# Module_Connector_Male.net
KiCad netlist of a schematic drawn in Altium Designer
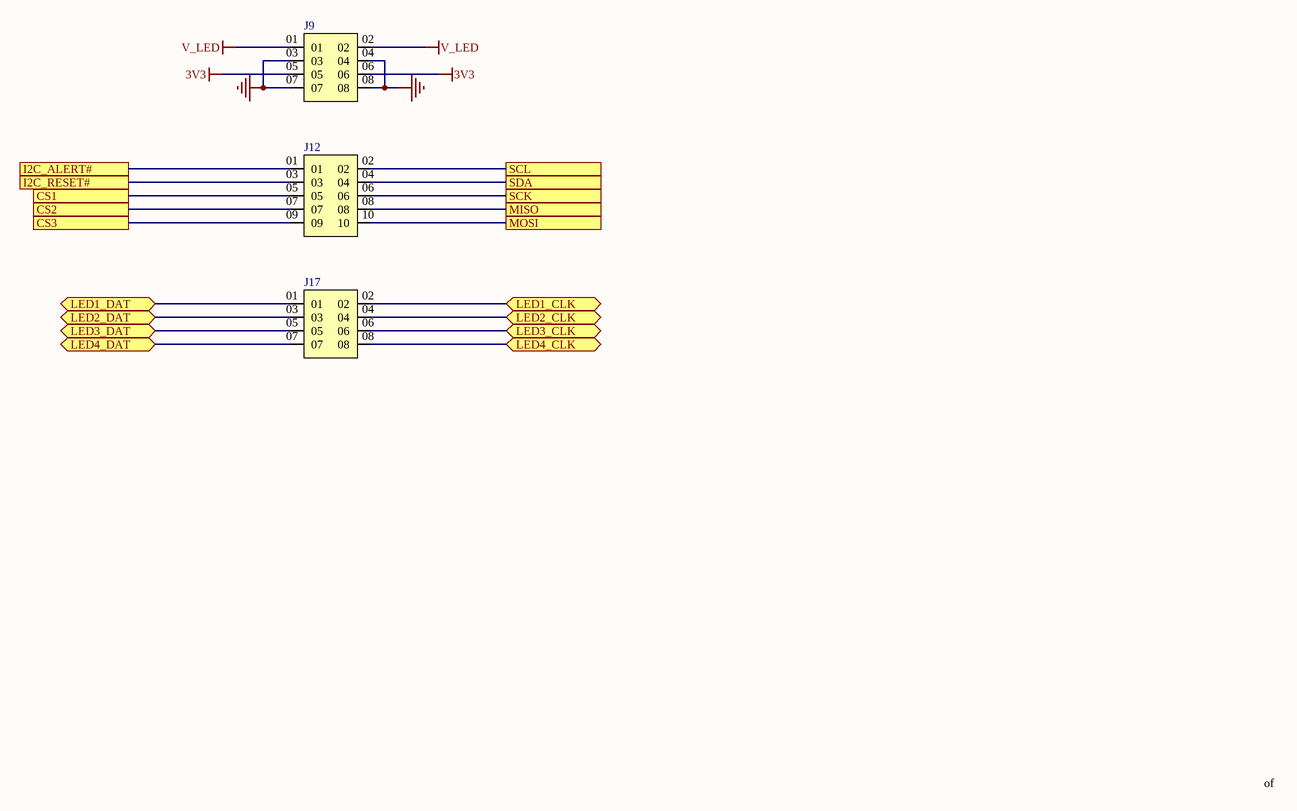
[diagram p0: Module Connector Male.SchDoc]

(export (version "E")
  (design (tool "Eeschema 10.0.6"))
  (components
    (comp (ref "J9")
      (value "Header 4x2 0.1\" RA")
      (footprint "Header 4x2 0.1\" RA")
      (description "Board Connector, 8 Contact(s), 2 Row(s), Female, Right Angle, 0.1 inch Pitch")
      (libsource (lib "Equus Computer Systems") (part "Header 4x2"))
    )
    (comp (ref "J12")
      (value "Header 5x2 0.1\" RA")
      (footprint "Header 5x2 0.1\" RA")
      (description "Board Connector, 10 Contact(s), 2 Row(s), Female, Right Angle, 0.1 inch Pitch")
      (libsource (lib "Equus Computer Systems") (part "Header 5x2 0.1{dblquote}"))
    )
    (comp (ref "J17")
      (value "Header 4x2 0.1\" RA")
      (footprint "Header 4x2 0.1\" RA")
      (description "Board Connector, 8 Contact(s), 2 Row(s), Female, Right Angle, 0.1 inch Pitch")
      (libsource (lib "Equus Computer Systems") (part "Header 4x2"))
    )
  )
  (nets
    (net (code "1") (name "/CS1") (class "Default")
      (node (ref "J12") (pin "05") (pinfunction "05_05") (pintype "passive"))
    )
    (net (code "2") (name "/CS2") (class "Default")
      (node (ref "J12") (pin "07") (pinfunction "07_07") (pintype "passive"))
    )
    (net (code "3") (name "/CS3") (class "Default")
      (node (ref "J12") (pin "09") (pinfunction "09_09") (pintype "passive"))
    )
    (net (code "4") (name "/I2C_ALERT#") (class "Default")
      (node (ref "J12") (pin "01") (pinfunction "01_01") (pintype "passive"))
    )
    (net (code "5") (name "/I2C_RESET#") (class "Default")
      (node (ref "J12") (pin "03") (pinfunction "03_03") (pintype "passive"))
    )
    (net (code "6") (name "/LED1_CLK") (class "Default")
      (node (ref "J17") (pin "02") (pinfunction "02_02") (pintype "passive"))
    )
    (net (code "7") (name "/LED1_DAT") (class "Default")
      (node (ref "J17") (pin "01") (pinfunction "01_01") (pintype "passive"))
    )
    (net (code "8") (name "/LED2_CLK") (class "Default")
      (node (ref "J17") (pin "04") (pinfunction "04_04") (pintype "passive"))
    )
    (net (code "9") (name "/LED2_DAT") (class "Default")
      (node (ref "J17") (pin "03") (pinfunction "03_03") (pintype "passive"))
    )
    (net (code "10") (name "/LED3_CLK") (class "Default")
      (node (ref "J17") (pin "06") (pinfunction "06_06") (pintype "passive"))
    )
    (net (code "11") (name "/LED3_DAT") (class "Default")
      (node (ref "J17") (pin "05") (pinfunction "05_05") (pintype "passive"))
    )
    (net (code "12") (name "/LED4_CLK") (class "Default")
      (node (ref "J17") (pin "08") (pinfunction "08_08") (pintype "passive"))
    )
    (net (code "13") (name "/LED4_DAT") (class "Default")
      (node (ref "J17") (pin "07") (pinfunction "07_07") (pintype "passive"))
    )
    (net (code "14") (name "/MISO") (class "Default")
      (node (ref "J12") (pin "08") (pinfunction "08_08") (pintype "passive"))
    )
    (net (code "15") (name "/MOSI") (class "Default")
      (node (ref "J12") (pin "10") (pinfunction "10_10") (pintype "passive"))
    )
    (net (code "16") (name "/SCK") (class "Default")
      (node (ref "J12") (pin "06") (pinfunction "06_06") (pintype "passive"))
    )
    (net (code "17") (name "/SCL") (class "Default")
      (node (ref "J12") (pin "02") (pinfunction "02_02") (pintype "passive"))
    )
    (net (code "18") (name "/SDA") (class "Default")
      (node (ref "J12") (pin "04") (pinfunction "04_04") (pintype "passive"))
    )
    (net (code "19") (name "3V3") (class "Default")
      (node (ref "J9") (pin "05") (pinfunction "05_05") (pintype "passive"))
      (node (ref "J9") (pin "06") (pinfunction "06_06") (pintype "passive"))
    )
    (net (code "20") (name "GND") (class "Default")
      (node (ref "J9") (pin "03") (pinfunction "03_03") (pintype "passive"))
      (node (ref "J9") (pin "04") (pinfunction "04_04") (pintype "passive"))
      (node (ref "J9") (pin "07") (pinfunction "07_07") (pintype "passive"))
      (node (ref "J9") (pin "08") (pinfunction "08_08") (pintype "passive"))
    )
    (net (code "21") (name "V_LED") (class "Default")
      (node (ref "J9") (pin "01") (pinfunction "01_01") (pintype "passive"))
      (node (ref "J9") (pin "02") (pinfunction "02_02") (pintype "passive"))
    )
  )
)
